# hall_sensor.net
KiCad netlist of a schematic drawn in Altium Designer
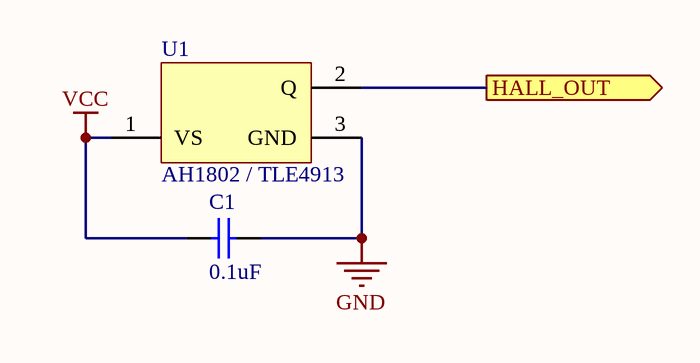
[diagram p0: hall_sensor.SchDoc]

(export (version "E")
  (design (tool "Eeschema 10.0.6"))
  (components
    (comp (ref "C1")
      (value "0.1uF")
      (footprint "CAPC1608X87X35NL15T15")
      (fields (field (name "PART NUMBER") "C0603X104K5RACTU") (field (name "MANUFACTURER") "Kemet"))
      (libsource (lib "Altium Content Vault") (part "CAP"))
    )
    (comp (ref "U1")
      (value "AH1802 / TLE4913")
      (footprint "INF-PG-SC59_M")
      (description "Low Power Hall Switch, PG-SC59, Reel, Green")
      (fields (field (name "MANUFACTURER") "Infineon") (field (name "PARTNUMBER") "AH1802"))
      (libsource (lib "Altium Content Vault") (part "INF-TLE49XX-SC59-3"))
    )
  )
  (nets
    (net (code "1") (name "/HALL_OUT") (class "Default")
      (node (ref "U1") (pin "2") (pinfunction "Q_2") (pintype "open_collector"))
    )
    (net (code "2") (name "GND") (class "Default")
      (node (ref "C1") (pin "2") (pinfunction "2_2") (pintype "passive"))
      (node (ref "U1") (pin "3") (pinfunction "GND_3") (pintype "power_in"))
    )
    (net (code "3") (name "VCC") (class "Default")
      (node (ref "C1") (pin "1") (pinfunction "1_1") (pintype "passive"))
      (node (ref "U1") (pin "1") (pinfunction "VS_1") (pintype "power_in"))
    )
  )
)
